# DS3231_ClockLed.net
KiCad netlist of a schematic drawn in Altium Designer
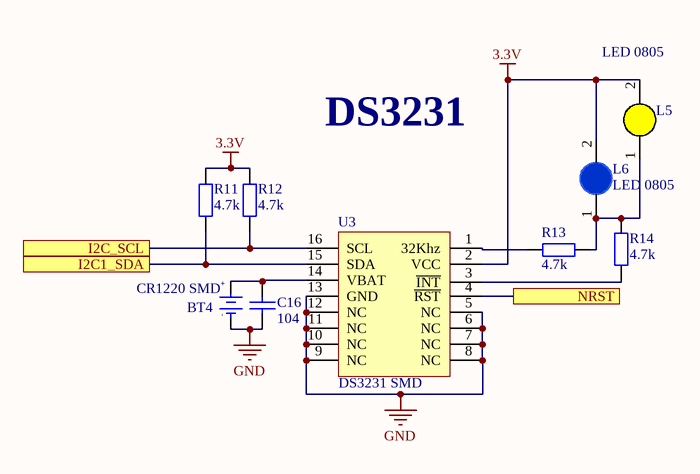
[diagram p0: DS3231_ClockLed.SchDoc]

(export (version "E")
  (design (tool "Eeschema 10.0.6"))
  (components
    (comp (ref "BT4")
      (value "CR1220 SMD")
      (footprint "DE PIN CR1220")
      (libsource (lib "Altium_Lib_by_KhueNguyenCreator") (part "De pin CR1220 SMD"))
    )
    (comp (ref "C16")
      (value "104")
      (footprint "tu 0805")
      (description "Dán")
      (libsource (lib "Altium_Lib_by_KhueNguyenCreator") (part "Tu 0805 104 50V 10%"))
    )
    (comp (ref "L5")
      (value "LED 0805")
      (footprint "LED-1206-Yellow")
      (description "Dán")
      (libsource (lib "Altium_Lib_by_KhueNguyenCreator") (part "LED 1206 Vang"))
    )
    (comp (ref "L6")
      (value "LED 0805")
      (footprint "LED-0805-Blue")
      (description "Dán")
      (libsource (lib "Altium_Lib_by_KhueNguyenCreator") (part "LED 0805 Xanh Duong"))
    )
    (comp (ref "R11")
      (value "4.7k")
      (footprint "tro smd 0805")
      (description "Dán")
      (libsource (lib "Altium_Lib_by_KhueNguyenCreator") (part "Tro 0805 5% 4.7k"))
    )
    (comp (ref "R12")
      (value "4.7k")
      (footprint "tro smd 0805")
      (description "Dán")
      (libsource (lib "Altium_Lib_by_KhueNguyenCreator") (part "Tro 0805 5% 4.7k"))
    )
    (comp (ref "R13")
      (value "4.7k")
      (footprint "tro smd 0805")
      (description "Dán")
      (libsource (lib "Altium_Lib_by_KhueNguyenCreator") (part "Tro 0805 5% 4.7k"))
    )
    (comp (ref "R14")
      (value "4.7k")
      (footprint "tro smd 0805")
      (description "Dán")
      (libsource (lib "Altium_Lib_by_KhueNguyenCreator") (part "Tro 0805 5% 4.7k"))
    )
    (comp (ref "U3")
      (value "DS3231 SMD")
      (footprint "SOIC 16")
      (description "SOIC")
      (libsource (lib "Altium_Lib_by_KhueNguyenCreator") (part "DS3231 SMD"))
    )
  )
  (nets
    (net (code "1") (name "/I2C1_SDA") (class "Default")
      (node (ref "R11") (pin "1") (pinfunction "1_1") (pintype "passive"))
      (node (ref "U3") (pin "15") (pinfunction "SDA_15") (pintype "power_in"))
    )
    (net (code "2") (name "/I2C_SCL") (class "Default")
      (node (ref "R12") (pin "1") (pinfunction "1_1") (pintype "passive"))
      (node (ref "U3") (pin "16") (pinfunction "SCL_16") (pintype "power_in"))
    )
    (net (code "3") (name "/NRST") (class "Default")
      (node (ref "U3") (pin "4") (pinfunction "~{RST}_4") (pintype "power_in"))
    )
    (net (code "4") (name "3.3V") (class "Default")
      (node (ref "L5") (pin "2") (pinfunction "K_2") (pintype "passive"))
      (node (ref "L6") (pin "2") (pinfunction "K_2") (pintype "passive"))
      (node (ref "R11") (pin "2") (pinfunction "2_2") (pintype "passive"))
      (node (ref "R12") (pin "2") (pinfunction "2_2") (pintype "passive"))
      (node (ref "U3") (pin "2") (pinfunction "VCC_2") (pintype "power_in"))
    )
    (net (code "5") (name "GND") (class "Default")
      (node (ref "BT4") (pin "2") (pinfunction "GND_2") (pintype "passive"))
      (node (ref "C16") (pin "2") (pinfunction "2_2") (pintype "passive"))
      (node (ref "U3") (pin "10") (pinfunction "NC_10") (pintype "power_in"))
      (node (ref "U3") (pin "11") (pinfunction "NC_11") (pintype "power_in"))
      (node (ref "U3") (pin "12") (pinfunction "NC_12") (pintype "power_in"))
      (node (ref "U3") (pin "13") (pinfunction "GND_13") (pintype "power_in"))
      (node (ref "U3") (pin "5") (pinfunction "NC_5") (pintype "power_in"))
      (node (ref "U3") (pin "6") (pinfunction "NC_6") (pintype "power_in"))
      (node (ref "U3") (pin "7") (pinfunction "NC_7") (pintype "power_in"))
      (node (ref "U3") (pin "8") (pinfunction "NC_8") (pintype "power_in"))
      (node (ref "U3") (pin "9") (pinfunction "NC_9") (pintype "power_in"))
    )
    (net (code "6") (name "Net-(BT4-+3V)") (class "Default")
      (node (ref "BT4") (pin "1") (pinfunction "+3V_1") (pintype "passive"))
      (node (ref "C16") (pin "1") (pinfunction "1_1") (pintype "passive"))
      (node (ref "U3") (pin "14") (pinfunction "VBAT_14") (pintype "power_in"))
    )
    (net (code "7") (name "Net-(L5-A)") (class "Default")
      (node (ref "L5") (pin "1") (pinfunction "A_1") (pintype "passive"))
      (node (ref "L6") (pin "1") (pinfunction "A_1") (pintype "passive"))
      (node (ref "R13") (pin "1") (pinfunction "1_1") (pintype "passive"))
      (node (ref "R14") (pin "1") (pinfunction "1_1") (pintype "passive"))
    )
    (net (code "8") (name "Net-(U3-32Khz)") (class "Default")
      (node (ref "R13") (pin "2") (pinfunction "2_2") (pintype "passive"))
      (node (ref "U3") (pin "1") (pinfunction "32Khz_1") (pintype "power_in"))
    )
    (net (code "9") (name "Net-(U3-~{INT})") (class "Default")
      (node (ref "R14") (pin "2") (pinfunction "2_2") (pintype "passive"))
      (node (ref "U3") (pin "3") (pinfunction "~{INT}_3") (pintype "power_in"))
    )
  )
)
